# 07_-_LIGHTS.net
KiCad netlist of a schematic drawn in Altium Designer
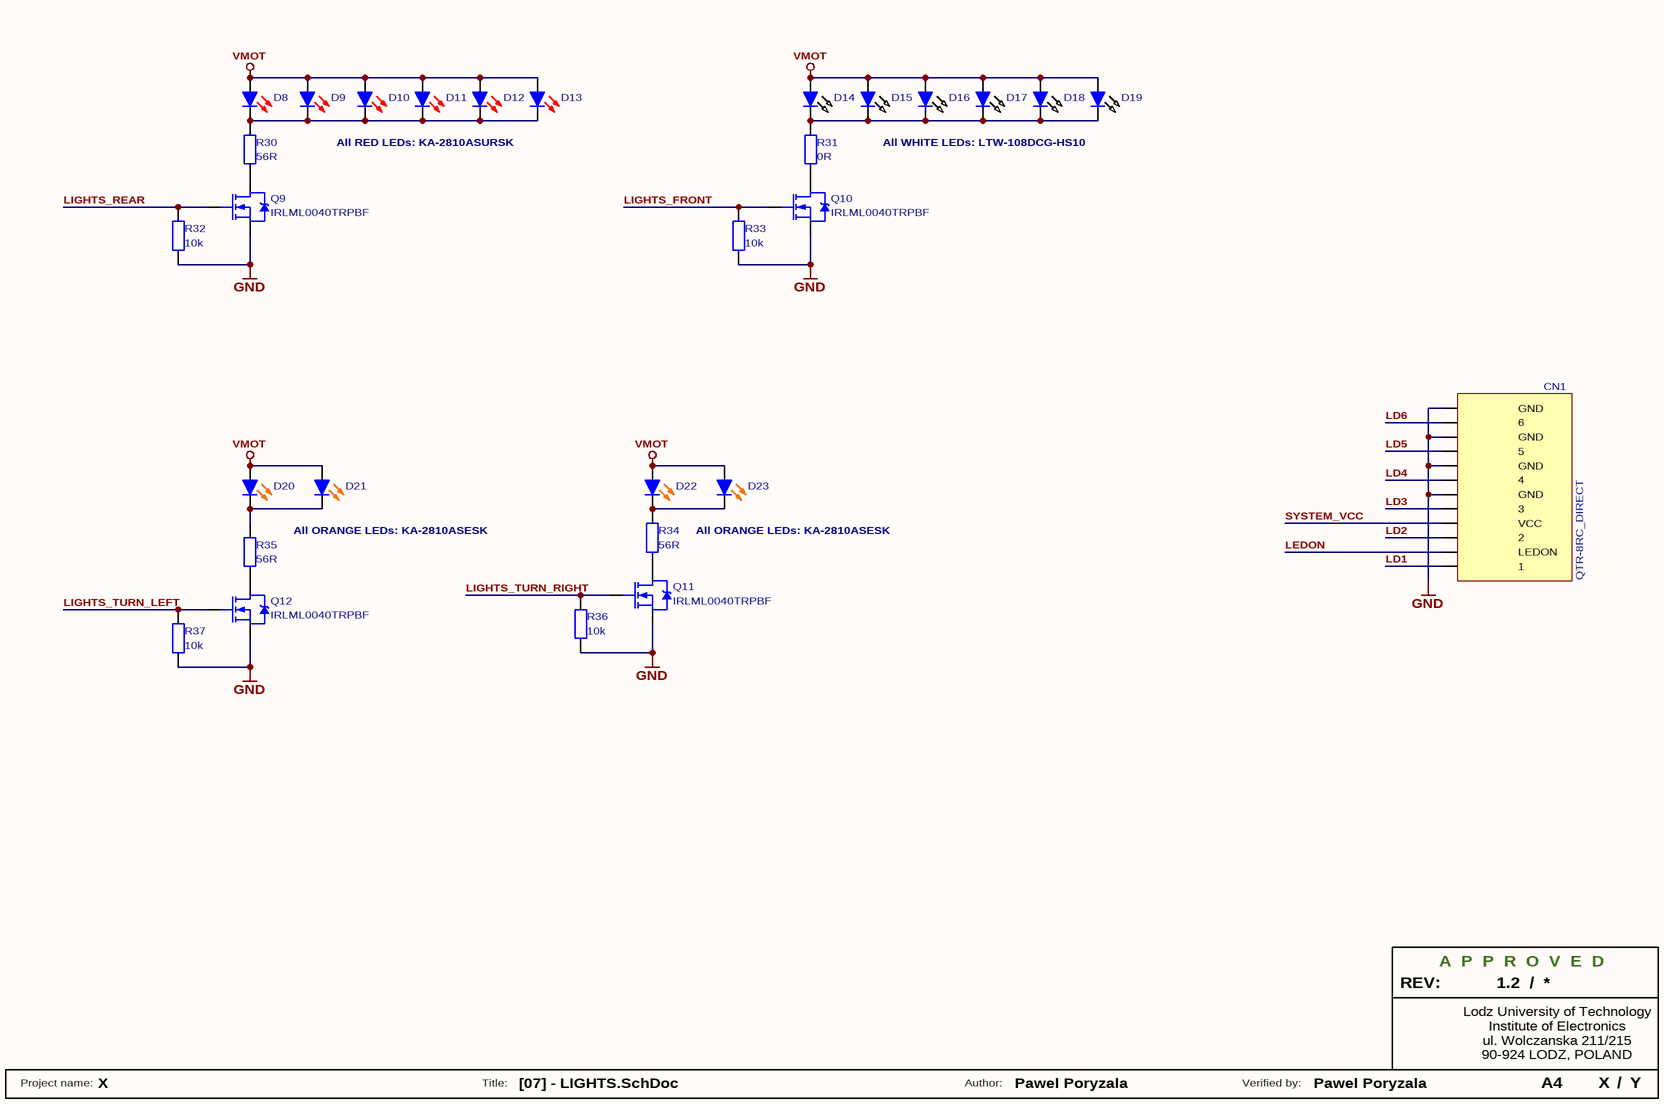
[diagram p0: [07] - LIGHTS.SchDoc]

(export (version "E")
  (design (tool "Eeschema 10.0.6"))
  (components
    (comp (ref "CN1")
      (value "QTR-8RC_DIRECT")
      (footprint "QTR-8RC_SNAPPED_GOLDPIN_VERTICAL")
      (description "QTR-8RC Reflectance Sensor Array (Pololu item No. 961)")
      (libsource (lib "other_modules") (part "QTR-8RC_DIRECT"))
    )
    (comp (ref "D8")
      (value "KA-2810ASURSK")
      (footprint "LED2810")
      (libsource (lib "leds") (part "KA-2810ASURSK"))
    )
    (comp (ref "D9")
      (value "KA-2810ASURSK")
      (footprint "LED2810")
      (libsource (lib "leds") (part "KA-2810ASURSK"))
    )
    (comp (ref "D10")
      (value "KA-2810ASURSK")
      (footprint "LED2810")
      (libsource (lib "leds") (part "KA-2810ASURSK"))
    )
    (comp (ref "D11")
      (value "KA-2810ASURSK")
      (footprint "LED2810")
      (libsource (lib "leds") (part "KA-2810ASURSK"))
    )
    (comp (ref "D12")
      (value "KA-2810ASURSK")
      (footprint "LED2810")
      (libsource (lib "leds") (part "KA-2810ASURSK"))
    )
    (comp (ref "D13")
      (value "KA-2810ASURSK")
      (footprint "LED2810")
      (libsource (lib "leds") (part "KA-2810ASURSK"))
    )
    (comp (ref "D14")
      (value "LTW-108DCG-HS10")
      (footprint "LED2810")
      (libsource (lib "leds") (part "LTW-108DCG-HS10"))
    )
    (comp (ref "D15")
      (value "LTW-108DCG-HS10")
      (footprint "LED2810")
      (libsource (lib "leds") (part "LTW-108DCG-HS10"))
    )
    (comp (ref "D16")
      (value "LTW-108DCG-HS10")
      (footprint "LED2810")
      (libsource (lib "leds") (part "LTW-108DCG-HS10"))
    )
    (comp (ref "D17")
      (value "LTW-108DCG-HS10")
      (footprint "LED2810")
      (libsource (lib "leds") (part "LTW-108DCG-HS10"))
    )
    (comp (ref "D18")
      (value "LTW-108DCG-HS10")
      (footprint "LED2810")
      (libsource (lib "leds") (part "LTW-108DCG-HS10"))
    )
    (comp (ref "D19")
      (value "LTW-108DCG-HS10")
      (footprint "LED2810")
      (libsource (lib "leds") (part "LTW-108DCG-HS10"))
    )
    (comp (ref "D20")
      (value "KA-2810ASESK")
      (footprint "LED2810")
      (libsource (lib "leds") (part "KA-2810ASESK"))
    )
    (comp (ref "D21")
      (value "KA-2810ASESK")
      (footprint "LED2810")
      (libsource (lib "leds") (part "KA-2810ASESK"))
    )
    (comp (ref "D22")
      (value "KA-2810ASESK")
      (footprint "LED2810")
      (libsource (lib "leds") (part "KA-2810ASESK"))
    )
    (comp (ref "D23")
      (value "KA-2810ASESK")
      (footprint "LED2810")
      (libsource (lib "leds") (part "KA-2810ASESK"))
    )
    (comp (ref "Q9")
      (value "IRLML0040TRPBF")
      (footprint "SOT-23")
      (description "N-Channel; 40V, 3.6A, 1,25W; HEXFET Power MOS-FET")
      (libsource (lib "transistors_mos") (part "IRLML0040TRPBF"))
    )
    (comp (ref "Q10")
      (value "IRLML0040TRPBF")
      (footprint "SOT-23")
      (description "N-Channel; 40V, 3.6A, 1,25W; HEXFET Power MOS-FET")
      (libsource (lib "transistors_mos") (part "IRLML0040TRPBF"))
    )
    (comp (ref "Q11")
      (value "IRLML0040TRPBF")
      (footprint "SOT-23")
      (description "N-Channel; 40V, 3.6A, 1,25W; HEXFET Power MOS-FET")
      (libsource (lib "transistors_mos") (part "IRLML0040TRPBF"))
    )
    (comp (ref "Q12")
      (value "IRLML0040TRPBF")
      (footprint "SOT-23")
      (description "N-Channel; 40V, 3.6A, 1,25W; HEXFET Power MOS-FET")
      (libsource (lib "transistors_mos") (part "IRLML0040TRPBF"))
    )
    (comp (ref "R30")
      (value "56R")
      (footprint "R0805")
      (description "Resistor")
      (libsource (lib "resistors") (part "Res"))
    )
    (comp (ref "R31")
      (value "0R")
      (footprint "R0805")
      (description "Resistor")
      (libsource (lib "resistors") (part "Res"))
    )
    (comp (ref "R32")
      (value "10k")
      (footprint "R0805")
      (description "Resistor")
      (libsource (lib "resistors") (part "Res"))
    )
    (comp (ref "R33")
      (value "10k")
      (footprint "R0805")
      (description "Resistor")
      (libsource (lib "resistors") (part "Res"))
    )
    (comp (ref "R34")
      (value "56R")
      (footprint "R0805")
      (description "Resistor")
      (libsource (lib "resistors") (part "Res"))
    )
    (comp (ref "R35")
      (value "56R")
      (footprint "R0805")
      (description "Resistor")
      (libsource (lib "resistors") (part "Res"))
    )
    (comp (ref "R36")
      (value "10k")
      (footprint "R0805")
      (description "Resistor")
      (libsource (lib "resistors") (part "Res"))
    )
    (comp (ref "R37")
      (value "10k")
      (footprint "R0805")
      (description "Resistor")
      (libsource (lib "resistors") (part "Res"))
    )
  )
  (nets
    (net (code "1") (name "/LD1") (class "Default")
      (node (ref "CN1") (pin "1") (pinfunction "1_1") (pintype "passive"))
    )
    (net (code "2") (name "/LD2") (class "Default")
      (node (ref "CN1") (pin "2") (pinfunction "2_2") (pintype "passive"))
    )
    (net (code "3") (name "/LD3") (class "Default")
      (node (ref "CN1") (pin "3") (pinfunction "3_3") (pintype "passive"))
    )
    (net (code "4") (name "/LD4") (class "Default")
      (node (ref "CN1") (pin "4") (pinfunction "4_4") (pintype "passive"))
    )
    (net (code "5") (name "/LD5") (class "Default")
      (node (ref "CN1") (pin "5") (pinfunction "5_5") (pintype "passive"))
    )
    (net (code "6") (name "/LD6") (class "Default")
      (node (ref "CN1") (pin "6") (pinfunction "6_6") (pintype "passive"))
    )
    (net (code "7") (name "/LEDON") (class "Default")
      (node (ref "CN1") (pin "LEDON") (pinfunction "LEDON_LEDON") (pintype "passive"))
    )
    (net (code "8") (name "/LIGHTS_FRONT") (class "Default")
      (node (ref "Q10") (pin "1") (pinfunction "G_1") (pintype "passive"))
      (node (ref "R33") (pin "1") (pinfunction "1_1") (pintype "passive"))
    )
    (net (code "9") (name "/LIGHTS_REAR") (class "Default")
      (node (ref "Q9") (pin "1") (pinfunction "G_1") (pintype "passive"))
      (node (ref "R32") (pin "1") (pinfunction "1_1") (pintype "passive"))
    )
    (net (code "10") (name "/LIGHTS_TURN_LEFT") (class "Default")
      (node (ref "Q12") (pin "1") (pinfunction "G_1") (pintype "passive"))
      (node (ref "R37") (pin "1") (pinfunction "1_1") (pintype "passive"))
    )
    (net (code "11") (name "/LIGHTS_TURN_RIGHT") (class "Default")
      (node (ref "Q11") (pin "1") (pinfunction "G_1") (pintype "passive"))
      (node (ref "R36") (pin "1") (pinfunction "1_1") (pintype "passive"))
    )
    (net (code "12") (name "/SYSTEM_VCC") (class "Default")
      (node (ref "CN1") (pin "VCC") (pinfunction "VCC_VCC") (pintype "passive"))
    )
    (net (code "13") (name "GND") (class "Default")
      (node (ref "CN1") (pin "GND") (pinfunction "GND_GND") (pintype "passive"))
      (node (ref "Q10") (pin "2") (pinfunction "S_2") (pintype "passive"))
      (node (ref "Q11") (pin "2") (pinfunction "S_2") (pintype "passive"))
      (node (ref "Q12") (pin "2") (pinfunction "S_2") (pintype "passive"))
      (node (ref "Q9") (pin "2") (pinfunction "S_2") (pintype "passive"))
      (node (ref "R32") (pin "2") (pinfunction "2_2") (pintype "passive"))
      (node (ref "R33") (pin "2") (pinfunction "2_2") (pintype "passive"))
      (node (ref "R36") (pin "2") (pinfunction "2_2") (pintype "passive"))
      (node (ref "R37") (pin "2") (pinfunction "2_2") (pintype "passive"))
    )
    (net (code "14") (name "Net-(D10-K)") (class "Default")
      (node (ref "D10") (pin "1") (pinfunction "K_1") (pintype "passive"))
      (node (ref "D11") (pin "1") (pinfunction "K_1") (pintype "passive"))
      (node (ref "D12") (pin "1") (pinfunction "K_1") (pintype "passive"))
      (node (ref "D13") (pin "1") (pinfunction "K_1") (pintype "passive"))
      (node (ref "D8") (pin "1") (pinfunction "K_1") (pintype "passive"))
      (node (ref "D9") (pin "1") (pinfunction "K_1") (pintype "passive"))
      (node (ref "R30") (pin "1") (pinfunction "1_1") (pintype "passive"))
    )
    (net (code "15") (name "Net-(D14-K)") (class "Default")
      (node (ref "D14") (pin "1") (pinfunction "K_1") (pintype "passive"))
      (node (ref "D15") (pin "1") (pinfunction "K_1") (pintype "passive"))
      (node (ref "D16") (pin "1") (pinfunction "K_1") (pintype "passive"))
      (node (ref "D17") (pin "1") (pinfunction "K_1") (pintype "passive"))
      (node (ref "D18") (pin "1") (pinfunction "K_1") (pintype "passive"))
      (node (ref "D19") (pin "1") (pinfunction "K_1") (pintype "passive"))
      (node (ref "R31") (pin "1") (pinfunction "1_1") (pintype "passive"))
    )
    (net (code "16") (name "Net-(D20-K)") (class "Default")
      (node (ref "D20") (pin "1") (pinfunction "K_1") (pintype "passive"))
      (node (ref "D21") (pin "1") (pinfunction "K_1") (pintype "passive"))
      (node (ref "R35") (pin "1") (pinfunction "1_1") (pintype "passive"))
    )
    (net (code "17") (name "Net-(D22-K)") (class "Default")
      (node (ref "D22") (pin "1") (pinfunction "K_1") (pintype "passive"))
      (node (ref "D23") (pin "1") (pinfunction "K_1") (pintype "passive"))
      (node (ref "R34") (pin "1") (pinfunction "1_1") (pintype "passive"))
    )
    (net (code "18") (name "Net-(Q9-D)") (class "Default")
      (node (ref "Q9") (pin "3") (pinfunction "D_3") (pintype "passive"))
      (node (ref "R30") (pin "2") (pinfunction "2_2") (pintype "passive"))
    )
    (net (code "19") (name "Net-(Q10-D)") (class "Default")
      (node (ref "Q10") (pin "3") (pinfunction "D_3") (pintype "passive"))
      (node (ref "R31") (pin "2") (pinfunction "2_2") (pintype "passive"))
    )
    (net (code "20") (name "Net-(Q11-D)") (class "Default")
      (node (ref "Q11") (pin "3") (pinfunction "D_3") (pintype "passive"))
      (node (ref "R34") (pin "2") (pinfunction "2_2") (pintype "passive"))
    )
    (net (code "21") (name "Net-(Q12-D)") (class "Default")
      (node (ref "Q12") (pin "3") (pinfunction "D_3") (pintype "passive"))
      (node (ref "R35") (pin "2") (pinfunction "2_2") (pintype "passive"))
    )
    (net (code "22") (name "VMOT") (class "Default")
      (node (ref "D10") (pin "2") (pinfunction "A_2") (pintype "passive"))
      (node (ref "D11") (pin "2") (pinfunction "A_2") (pintype "passive"))
      (node (ref "D12") (pin "2") (pinfunction "A_2") (pintype "passive"))
      (node (ref "D13") (pin "2") (pinfunction "A_2") (pintype "passive"))
      (node (ref "D14") (pin "2") (pinfunction "A_2") (pintype "passive"))
      (node (ref "D15") (pin "2") (pinfunction "A_2") (pintype "passive"))
      (node (ref "D16") (pin "2") (pinfunction "A_2") (pintype "passive"))
      (node (ref "D17") (pin "2") (pinfunction "A_2") (pintype "passive"))
      (node (ref "D18") (pin "2") (pinfunction "A_2") (pintype "passive"))
      (node (ref "D19") (pin "2") (pinfunction "A_2") (pintype "passive"))
      (node (ref "D20") (pin "2") (pinfunction "A_2") (pintype "passive"))
      (node (ref "D21") (pin "2") (pinfunction "A_2") (pintype "passive"))
      (node (ref "D22") (pin "2") (pinfunction "A_2") (pintype "passive"))
      (node (ref "D23") (pin "2") (pinfunction "A_2") (pintype "passive"))
      (node (ref "D8") (pin "2") (pinfunction "A_2") (pintype "passive"))
      (node (ref "D9") (pin "2") (pinfunction "A_2") (pintype "passive"))
    )
  )
)
